# 20210416-JGaylord-FuzzCracklePlus.net
KiCad netlist of a schematic drawn in EAGLE
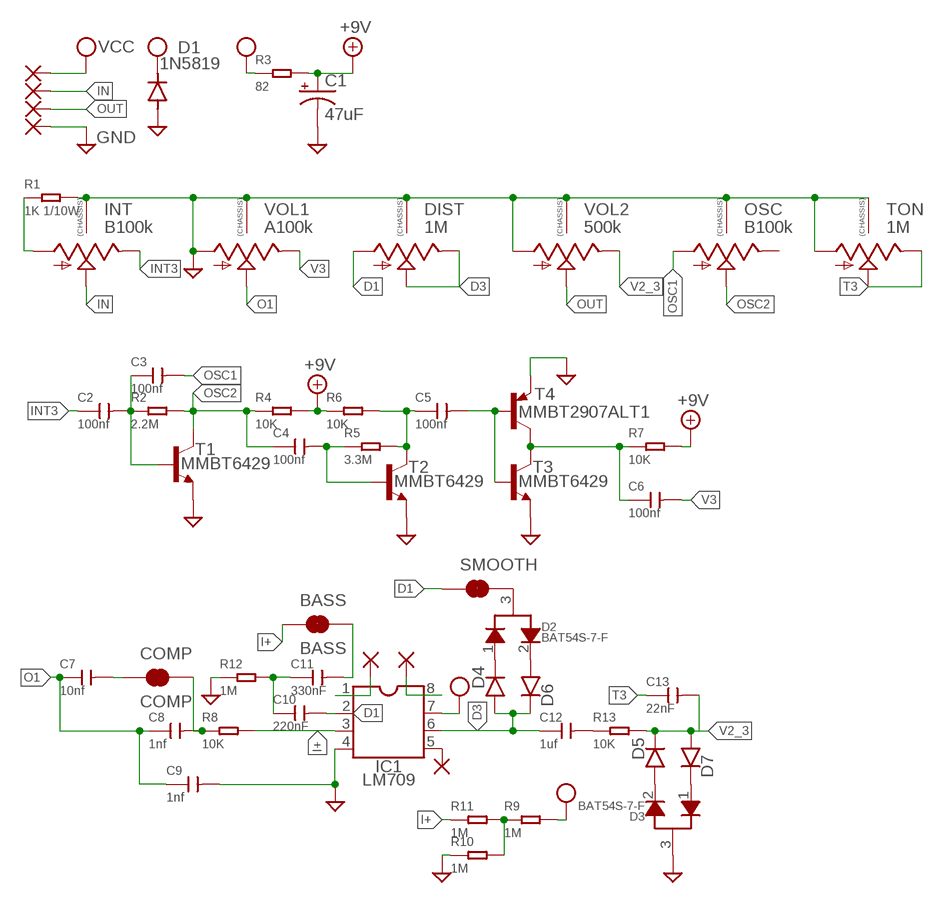
[diagram p0: schematic, sheet 1]

(export (version "E")
  (design (tool "Eeschema 10.0.6"))
  (components
    (comp (ref "BASS")
      (value "BASS")
      (footprint "eagle-import:SMT-JUMPER_2_NC_TRACE_SILK")
      (libsource (lib "eagle-import") (part "JUMPER-SMT_2_NC_TRACE_SILK"))
    )
    (comp (ref "C1")
      (value "47uF")
      (footprint "eagle-import:CPOL-RADIAL-2.5MM-6.5MM")
      (libsource (lib "eagle-import") (part "100UF-POLAR-RADIAL-2.5MM-25V-20%"))
    )
    (comp (ref "C2")
      (value "100nf")
      (footprint "eagle-import:C0603")
      (fields (field (name "MPN") "CC0603KRX7R9BB104"))
      (libsource (lib "eagle-import") (part "CERAMIC-100NF-50V-10%-X7R(0603)"))
    )
    (comp (ref "C3")
      (value "100nf")
      (footprint "eagle-import:C0603")
      (fields (field (name "MPN") "CC0603KRX7R9BB104"))
      (libsource (lib "eagle-import") (part "CERAMIC-100NF-50V-10%-X7R(0603)"))
    )
    (comp (ref "C4")
      (value "100nf")
      (footprint "eagle-import:C0603")
      (fields (field (name "MPN") "CC0603KRX7R9BB104"))
      (libsource (lib "eagle-import") (part "CERAMIC-100NF-50V-10%-X7R(0603)"))
    )
    (comp (ref "C5")
      (value "100nf")
      (footprint "eagle-import:C0603")
      (fields (field (name "MPN") "CC0603KRX7R9BB104"))
      (libsource (lib "eagle-import") (part "CERAMIC-100NF-50V-10%-X7R(0603)"))
    )
    (comp (ref "C6")
      (value "100nf")
      (footprint "eagle-import:C0603")
      (fields (field (name "MPN") "CC0603KRX7R9BB104"))
      (libsource (lib "eagle-import") (part "CERAMIC-100NF-50V-10%-X7R(0603)"))
    )
    (comp (ref "C7")
      (value "10nf")
      (footprint "eagle-import:C0603")
      (fields (field (name "MPN") "CC0603KRX7R9BB104"))
      (libsource (lib "eagle-import") (part "CERAMIC-100NF-50V-10%-X7R(0603)"))
    )
    (comp (ref "C8")
      (value "1nf")
      (footprint "eagle-import:C0603")
      (fields (field (name "MPN") "CC0603KRX7R9BB104"))
      (libsource (lib "eagle-import") (part "CERAMIC-100NF-50V-10%-X7R(0603)"))
    )
    (comp (ref "C9")
      (value "1nf")
      (footprint "eagle-import:C0603")
      (fields (field (name "MPN") "CC0603KRX7R9BB104"))
      (libsource (lib "eagle-import") (part "CERAMIC-100NF-50V-10%-X7R(0603)"))
    )
    (comp (ref "C10")
      (value "220nF")
      (footprint "eagle-import:C0603")
      (fields (field (name "MPN") "CC0603KRX7R9BB104"))
      (libsource (lib "eagle-import") (part "CERAMIC-100NF-50V-10%-X7R(0603)"))
    )
    (comp (ref "C11")
      (value "330nF")
      (footprint "eagle-import:C0603")
      (fields (field (name "MPN") "CC0603KRX7R9BB104"))
      (libsource (lib "eagle-import") (part "CERAMIC-100NF-50V-10%-X7R(0603)"))
    )
    (comp (ref "C12")
      (value "1uf")
      (footprint "eagle-import:C0805")
      (fields (field (name "MPN") "CC0805KKX7R8BB105"))
      (libsource (lib "eagle-import") (part "CERAMIC-1UF-25V-10%-X7R(0805)"))
    )
    (comp (ref "C13")
      (value "22nF")
      (footprint "eagle-import:C0603")
      (fields (field (name "MPN") "CC0603KRX7R9BB104"))
      (libsource (lib "eagle-import") (part "CERAMIC-100NF-50V-10%-X7R(0603)"))
    )
    (comp (ref "COMP")
      (value "COMP")
      (footprint "eagle-import:SMT-JUMPER_2_NC_TRACE_SILK")
      (libsource (lib "eagle-import") (part "JUMPER-SMT_2_NC_TRACE_SILK"))
    )
    (comp (ref "D1")
      (value "1N5819")
      (footprint "eagle-import:SOD123")
      (libsource (lib "eagle-import") (part "DIODE-SOD123"))
    )
    (comp (ref "D2")
      (value "BAT54S-7-F")
      (footprint "eagle-import:SOT23-3")
      (fields
        (field (name "DIGIKEY_PART_NUMBER") "BAT54S-FDITR-ND")
        (field (name "MANUFACTURER") "Diodes Incorporated")
        (field (name "CREATED_BY") "PCBLayout.com")
      )
      (libsource (lib "eagle-import") (part "BAT54S-7-F"))
    )
    (comp (ref "D3")
      (value "BAT54S-7-F")
      (footprint "eagle-import:SOT23-3")
      (fields
        (field (name "DIGIKEY_PART_NUMBER") "BAT54S-FDITR-ND")
        (field (name "MANUFACTURER") "Diodes Incorporated")
        (field (name "CREATED_BY") "PCBLayout.com")
      )
      (libsource (lib "eagle-import") (part "BAT54S-7-F"))
    )
    (comp (ref "D4")
      (value "DO35.1")
      (footprint "eagle-import:DO41-1")
      (libsource (lib "eagle-import") (part "DO35.1"))
    )
    (comp (ref "D5")
      (value "DO35.1")
      (footprint "eagle-import:DO41-1")
      (libsource (lib "eagle-import") (part "DO35.1"))
    )
    (comp (ref "D6")
      (value "DO35.1")
      (footprint "eagle-import:DO41-1")
      (libsource (lib "eagle-import") (part "DO35.1"))
    )
    (comp (ref "D7")
      (value "DO35.1")
      (footprint "eagle-import:DO41-1")
      (libsource (lib "eagle-import") (part "DO35.1"))
    )
    (comp (ref "DIST")
      (value "1M")
      (footprint "eagle-import:9MM_SNAP-IN_POT")
      (libsource (lib "eagle-import") (part "9MM_SNAP-IN_POT_CHASSIS"))
    )
    (comp (ref "IC1")
      (value "LM709")
      (footprint "eagle-import:DIP08")
      (libsource (lib "eagle-import") (part "DIP8_TH"))
    )
    (comp (ref "INT")
      (value "B100k")
      (footprint "eagle-import:9MM_SNAP-IN_POT")
      (libsource (lib "eagle-import") (part "9MM_SNAP-IN_POT_CHASSIS"))
    )
    (comp (ref "NC")
      (value "1,6/0,8")
      (footprint "eagle-import:1,6_0,8")
      (libsource (lib "eagle-import") (part "1,6/0,8"))
    )
    (comp (ref "NC1")
      (value "1,6/0,8")
      (footprint "eagle-import:1,6_0,8")
      (libsource (lib "eagle-import") (part "1,6/0,8"))
    )
    (comp (ref "NC2")
      (value "1,6/0,8")
      (footprint "eagle-import:1,6_0,8")
      (libsource (lib "eagle-import") (part "1,6/0,8"))
    )
    (comp (ref "OSC")
      (value "B100k")
      (footprint "eagle-import:9MM_SNAP-IN_POT")
      (libsource (lib "eagle-import") (part "9MM_SNAP-IN_POT_CHASSIS"))
    )
    (comp (ref "PAD1")
      (value "1,6/0,8")
      (footprint "eagle-import:1,6_0,8")
      (libsource (lib "eagle-import") (part "1,6/0,8"))
    )
    (comp (ref "PAD2")
      (value "1,6/0,8")
      (footprint "eagle-import:1,6_0,8")
      (libsource (lib "eagle-import") (part "1,6/0,8"))
    )
    (comp (ref "PAD3")
      (value "1,6/0,8")
      (footprint "eagle-import:1,6_0,8")
      (libsource (lib "eagle-import") (part "1,6/0,8"))
    )
    (comp (ref "PAD4")
      (value "1,6/0,8")
      (footprint "eagle-import:1,6_0,8")
      (libsource (lib "eagle-import") (part "1,6/0,8"))
    )
    (comp (ref "R1")
      (value "1K 1/10W")
      (footprint "eagle-import:R0603")
      (fields (field (name "MPN") "RC0603JR-071KL"))
      (libsource (lib "eagle-import") (part "SMD-RES-1K-5%-1/10W(0603)"))
    )
    (comp (ref "R2")
      (value "2.2M")
      (footprint "eagle-import:R0603")
      (fields (field (name "MPN") "RC0603FR-072ML"))
      (libsource (lib "eagle-import") (part "SMD-RES-2M-1%-1/10W(0603)"))
    )
    (comp (ref "R3")
      (value "82")
      (footprint "eagle-import:R0603")
      (fields (field (name "MPN") "RC0603FR-071K5L"))
      (libsource (lib "eagle-import") (part "SMD-RES-68R-5%-1/10W(0603)"))
    )
    (comp (ref "R4")
      (value "10K")
      (footprint "eagle-import:R0603")
      (fields (field (name "MPN") "RC0603FR-0710KL"))
      (libsource (lib "eagle-import") (part "SMD-RES-10K-1%-1/10W(0603)"))
    )
    (comp (ref "R5")
      (value "3.3M")
      (footprint "eagle-import:R0603")
      (fields (field (name "MPN") "RC0603FR-072ML"))
      (libsource (lib "eagle-import") (part "SMD-RES-2M-1%-1/10W(0603)"))
    )
    (comp (ref "R6")
      (value "10K")
      (footprint "eagle-import:R0603")
      (fields (field (name "MPN") "RC0603FR-0710KL"))
      (libsource (lib "eagle-import") (part "SMD-RES-10K-1%-1/10W(0603)"))
    )
    (comp (ref "R7")
      (value "10K")
      (footprint "eagle-import:R0603")
      (fields (field (name "MPN") "RC0603FR-0710KL"))
      (libsource (lib "eagle-import") (part "SMD-RES-10K-1%-1/10W(0603)"))
    )
    (comp (ref "R8")
      (value "10K")
      (footprint "eagle-import:R0603")
      (fields (field (name "MPN") "RC0603FR-0710KL"))
      (libsource (lib "eagle-import") (part "SMD-RES-10K-1%-1/10W(0603)"))
    )
    (comp (ref "R9")
      (value "1M")
      (footprint "eagle-import:R0603")
      (fields (field (name "MPN") "RC0603FR-0710KL"))
      (libsource (lib "eagle-import") (part "SMD-RES-10K-1%-1/10W(0603)"))
    )
    (comp (ref "R10")
      (value "1M")
      (footprint "eagle-import:R0603")
      (fields (field (name "MPN") "RC0603FR-0710KL"))
      (libsource (lib "eagle-import") (part "SMD-RES-10K-1%-1/10W(0603)"))
    )
    (comp (ref "R11")
      (value "1M")
      (footprint "eagle-import:R0603")
      (fields (field (name "MPN") "RC0603FR-0710KL"))
      (libsource (lib "eagle-import") (part "SMD-RES-10K-1%-1/10W(0603)"))
    )
    (comp (ref "R12")
      (value "1M")
      (footprint "eagle-import:R0603")
      (fields (field (name "MPN") "RC0603FR-0710KL"))
      (libsource (lib "eagle-import") (part "SMD-RES-10K-1%-1/10W(0603)"))
    )
    (comp (ref "R13")
      (value "10K")
      (footprint "eagle-import:R0603")
      (fields (field (name "MPN") "RC0603FR-0710KL"))
      (libsource (lib "eagle-import") (part "SMD-RES-10K-1%-1/10W(0603)"))
    )
    (comp (ref "SMOOTH")
      (value "JUMPER-SMT_2_NC_TRACE_SILK")
      (footprint "eagle-import:SMT-JUMPER_2_NC_TRACE_SILK")
      (libsource (lib "eagle-import") (part "JUMPER-SMT_2_NC_TRACE_SILK"))
    )
    (comp (ref "T1")
      (value "MMBT6429")
      (footprint "eagle-import:SOT23-BEC")
      (libsource (lib "eagle-import") (part "-NPN-SOT23-BECMMBT6429LT1"))
    )
    (comp (ref "T2")
      (value "MMBT6429")
      (footprint "eagle-import:SOT23-BEC")
      (libsource (lib "eagle-import") (part "-NPN-SOT23-BECMMBT6429LT1"))
    )
    (comp (ref "T3")
      (value "MMBT6429")
      (footprint "eagle-import:SOT23-BEC")
      (libsource (lib "eagle-import") (part "-NPN-SOT23-BECMMBT6429LT1"))
    )
    (comp (ref "T4")
      (value "MMBT2907ALT1")
      (footprint "eagle-import:SOT23-BEC")
      (libsource (lib "eagle-import") (part "-PNP-SOT23-BECMMBT2907ALT1"))
    )
    (comp (ref "TON")
      (value "1M")
      (footprint "eagle-import:9MM_SNAP-IN_POT")
      (libsource (lib "eagle-import") (part "9MM_SNAP-IN_POT_CHASSIS"))
    )
    (comp (ref "VOL1")
      (value "A100k")
      (footprint "eagle-import:9MM_SNAP-IN_POT")
      (libsource (lib "eagle-import") (part "9MM_SNAP-IN_POT_CHASSIS"))
    )
    (comp (ref "VOL2")
      (value "500k")
      (footprint "eagle-import:9MM_SNAP-IN_POT")
      (libsource (lib "eagle-import") (part "9MM_SNAP-IN_POT_CHASSIS"))
    )
  )
  (nets
    (net (code "1") (name "+9V") (class "Default")
      (node (ref "C1") (pin "1") (pinfunction "+_1") (pintype "passive"))
      (node (ref "R3") (pin "2") (pinfunction "2_2") (pintype "passive"))
      (node (ref "R4") (pin "2") (pinfunction "2_2") (pintype "passive"))
      (node (ref "R6") (pin "1") (pinfunction "1_1") (pintype "passive"))
      (node (ref "R7") (pin "2") (pinfunction "2_2") (pintype "passive"))
    )
    (net (code "2") (name "D1") (class "Default")
      (node (ref "C10") (pin "2") (pinfunction "2_2") (pintype "passive"))
      (node (ref "DIST") (pin "1") (pinfunction "A_1") (pintype "passive"))
      (node (ref "IC1") (pin "2") (pinfunction "2_2") (pintype "passive"))
      (node (ref "SMOOTH") (pin "1") (pinfunction "1_1") (pintype "passive"))
    )
    (net (code "3") (name "D3") (class "Default")
      (node (ref "C12") (pin "1") (pinfunction "1_1") (pintype "passive"))
      (node (ref "D4") (pin "A") (pinfunction "A_A") (pintype "passive"))
      (node (ref "D6") (pin "C") (pinfunction "C_C") (pintype "passive"))
      (node (ref "DIST") (pin "2") (pinfunction "S_2") (pintype "passive"))
      (node (ref "DIST") (pin "3") (pinfunction "E_3") (pintype "passive"))
      (node (ref "IC1") (pin "6") (pinfunction "6_6") (pintype "passive"))
    )
    (net (code "4") (name "GND") (class "Default")
      (node (ref "C1") (pin "2") (pinfunction "-_2") (pintype "passive"))
      (node (ref "C9") (pin "2") (pinfunction "2_2") (pintype "passive"))
      (node (ref "D1") (pin "A") (pinfunction "A_A") (pintype "passive"))
      (node (ref "D3") (pin "3") (pinfunction "3_3") (pintype "passive"))
      (node (ref "DIST") (pin "CHASSIS1") (pinfunction "P$1_CHASSIS1") (pintype "passive"))
      (node (ref "DIST") (pin "CHASSIS2") (pinfunction "P$1_CHASSIS2") (pintype "passive"))
      (node (ref "IC1") (pin "4") (pinfunction "4_4") (pintype "passive"))
      (node (ref "INT") (pin "CHASSIS1") (pinfunction "P$1_CHASSIS1") (pintype "passive"))
      (node (ref "INT") (pin "CHASSIS2") (pinfunction "P$1_CHASSIS2") (pintype "passive"))
      (node (ref "OSC") (pin "CHASSIS1") (pinfunction "P$1_CHASSIS1") (pintype "passive"))
      (node (ref "OSC") (pin "CHASSIS2") (pinfunction "P$1_CHASSIS2") (pintype "passive"))
      (node (ref "PAD4") (pin "1") (pinfunction "P_1") (pintype "passive"))
      (node (ref "R1") (pin "2") (pinfunction "2_2") (pintype "passive"))
      (node (ref "R10") (pin "1") (pinfunction "1_1") (pintype "passive"))
      (node (ref "R12") (pin "1") (pinfunction "1_1") (pintype "passive"))
      (node (ref "T1") (pin "E") (pinfunction "E_E") (pintype "passive"))
      (node (ref "T2") (pin "E") (pinfunction "E_E") (pintype "passive"))
      (node (ref "T3") (pin "E") (pinfunction "E_E") (pintype "passive"))
      (node (ref "T4") (pin "E") (pinfunction "E_E") (pintype "passive"))
      (node (ref "TON") (pin "1") (pinfunction "A_1") (pintype "passive"))
      (node (ref "TON") (pin "CHASSIS1") (pinfunction "P$1_CHASSIS1") (pintype "passive"))
      (node (ref "TON") (pin "CHASSIS2") (pinfunction "P$1_CHASSIS2") (pintype "passive"))
      (node (ref "VOL1") (pin "1") (pinfunction "A_1") (pintype "passive"))
      (node (ref "VOL1") (pin "CHASSIS1") (pinfunction "P$1_CHASSIS1") (pintype "passive"))
      (node (ref "VOL1") (pin "CHASSIS2") (pinfunction "P$1_CHASSIS2") (pintype "passive"))
      (node (ref "VOL2") (pin "1") (pinfunction "A_1") (pintype "passive"))
      (node (ref "VOL2") (pin "CHASSIS1") (pinfunction "P$1_CHASSIS1") (pintype "passive"))
      (node (ref "VOL2") (pin "CHASSIS2") (pinfunction "P$1_CHASSIS2") (pintype "passive"))
    )
    (net (code "5") (name "I+") (class "Default")
      (node (ref "BASS") (pin "1") (pinfunction "1_1") (pintype "passive"))
      (node (ref "IC1") (pin "3") (pinfunction "3_3") (pintype "passive"))
      (node (ref "R11") (pin "1") (pinfunction "1_1") (pintype "passive"))
      (node (ref "R8") (pin "2") (pinfunction "2_2") (pintype "passive"))
    )
    (net (code "6") (name "IN") (class "Default")
      (node (ref "INT") (pin "2") (pinfunction "S_2") (pintype "passive"))
      (node (ref "PAD2") (pin "1") (pinfunction "P_1") (pintype "passive"))
    )
    (net (code "7") (name "INT3") (class "Default")
      (node (ref "C2") (pin "1") (pinfunction "1_1") (pintype "passive"))
      (node (ref "INT") (pin "3") (pinfunction "E_3") (pintype "passive"))
    )
    (net (code "8") (name "Net-(BASS-Pad2)") (class "Default")
      (node (ref "BASS") (pin "2") (pinfunction "2_2") (pintype "passive"))
      (node (ref "C11") (pin "2") (pinfunction "2_2") (pintype "passive"))
    )
    (net (code "9") (name "Net-(C2-Pad2)") (class "Default")
      (node (ref "C2") (pin "2") (pinfunction "2_2") (pintype "passive"))
      (node (ref "C3") (pin "1") (pinfunction "1_1") (pintype "passive"))
      (node (ref "R2") (pin "1") (pinfunction "1_1") (pintype "passive"))
      (node (ref "T1") (pin "B") (pinfunction "B_B") (pintype "passive"))
    )
    (net (code "10") (name "Net-(C4-Pad2)") (class "Default")
      (node (ref "C4") (pin "2") (pinfunction "2_2") (pintype "passive"))
      (node (ref "R5") (pin "1") (pinfunction "1_1") (pintype "passive"))
      (node (ref "T2") (pin "B") (pinfunction "B_B") (pintype "passive"))
    )
    (net (code "11") (name "Net-(C5-Pad1)") (class "Default")
      (node (ref "C5") (pin "1") (pinfunction "1_1") (pintype "passive"))
      (node (ref "R5") (pin "2") (pinfunction "2_2") (pintype "passive"))
      (node (ref "R6") (pin "2") (pinfunction "2_2") (pintype "passive"))
      (node (ref "T2") (pin "C") (pinfunction "C_C") (pintype "passive"))
    )
    (net (code "12") (name "Net-(C5-Pad2)") (class "Default")
      (node (ref "C5") (pin "2") (pinfunction "2_2") (pintype "passive"))
      (node (ref "T3") (pin "B") (pinfunction "B_B") (pintype "passive"))
      (node (ref "T4") (pin "B") (pinfunction "B_B") (pintype "passive"))
    )
    (net (code "13") (name "Net-(C6-Pad1)") (class "Default")
      (node (ref "C6") (pin "1") (pinfunction "1_1") (pintype "passive"))
      (node (ref "R7") (pin "1") (pinfunction "1_1") (pintype "passive"))
      (node (ref "T3") (pin "C") (pinfunction "C_C") (pintype "passive"))
      (node (ref "T4") (pin "C") (pinfunction "C_C") (pintype "passive"))
    )
    (net (code "14") (name "Net-(C7-Pad2)") (class "Default")
      (node (ref "C7") (pin "2") (pinfunction "2_2") (pintype "passive"))
      (node (ref "COMP") (pin "1") (pinfunction "1_1") (pintype "passive"))
    )
    (net (code "15") (name "Net-(C8-Pad2)") (class "Default")
      (node (ref "C8") (pin "2") (pinfunction "2_2") (pintype "passive"))
      (node (ref "COMP") (pin "2") (pinfunction "2_2") (pintype "passive"))
      (node (ref "R8") (pin "1") (pinfunction "1_1") (pintype "passive"))
    )
    (net (code "16") (name "Net-(C10-Pad1)") (class "Default")
      (node (ref "C10") (pin "1") (pinfunction "1_1") (pintype "passive"))
      (node (ref "C11") (pin "1") (pinfunction "1_1") (pintype "passive"))
      (node (ref "R12") (pin "2") (pinfunction "2_2") (pintype "passive"))
    )
    (net (code "17") (name "Net-(C12-Pad2)") (class "Default")
      (node (ref "C12") (pin "2") (pinfunction "2_2") (pintype "passive"))
      (node (ref "R13") (pin "1") (pinfunction "1_1") (pintype "passive"))
    )
    (net (code "18") (name "Net-(D2-Pad1)") (class "Default")
      (node (ref "D2") (pin "1") (pinfunction "1_1") (pintype "passive"))
      (node (ref "D4") (pin "C") (pinfunction "C_C") (pintype "passive"))
    )
    (net (code "19") (name "Net-(D2-Pad2)") (class "Default")
      (node (ref "D2") (pin "2") (pinfunction "2_2") (pintype "passive"))
      (node (ref "D6") (pin "A") (pinfunction "A_A") (pintype "passive"))
    )
    (net (code "20") (name "Net-(D2-Pad3)") (class "Default")
      (node (ref "D2") (pin "3") (pinfunction "3_3") (pintype "passive"))
      (node (ref "SMOOTH") (pin "2") (pinfunction "2_2") (pintype "passive"))
    )
    (net (code "21") (name "Net-(D3-Pad1)") (class "Default")
      (node (ref "D3") (pin "1") (pinfunction "1_1") (pintype "passive"))
      (node (ref "D7") (pin "C") (pinfunction "C_C") (pintype "passive"))
    )
    (net (code "22") (name "Net-(D3-Pad2)") (class "Default")
      (node (ref "D3") (pin "2") (pinfunction "2_2") (pintype "passive"))
      (node (ref "D5") (pin "A") (pinfunction "A_A") (pintype "passive"))
    )
    (net (code "23") (name "Net-(INT-A)") (class "Default")
      (node (ref "INT") (pin "1") (pinfunction "A_1") (pintype "passive"))
      (node (ref "R1") (pin "1") (pinfunction "1_1") (pintype "passive"))
    )
    (net (code "24") (name "Net-(NC-P)") (class "Default")
      (node (ref "IC1") (pin "1") (pinfunction "1_1") (pintype "passive"))
      (node (ref "NC") (pin "1") (pinfunction "P_1") (pintype "passive"))
    )
    (net (code "25") (name "Net-(NC1-P)") (class "Default")
      (node (ref "IC1") (pin "8") (pinfunction "8_8") (pintype "passive"))
      (node (ref "NC1") (pin "1") (pinfunction "P_1") (pintype "passive"))
    )
    (net (code "26") (name "Net-(NC2-P)") (class "Default")
      (node (ref "IC1") (pin "5") (pinfunction "5_5") (pintype "passive"))
      (node (ref "NC2") (pin "1") (pinfunction "P_1") (pintype "passive"))
    )
    (net (code "27") (name "Net-(R10-Pad2)") (class "Default")
      (node (ref "R10") (pin "2") (pinfunction "2_2") (pintype "passive"))
      (node (ref "R11") (pin "2") (pinfunction "2_2") (pintype "passive"))
      (node (ref "R9") (pin "1") (pinfunction "1_1") (pintype "passive"))
    )
    (net (code "28") (name "O1") (class "Default")
      (node (ref "C7") (pin "1") (pinfunction "1_1") (pintype "passive"))
      (node (ref "C8") (pin "1") (pinfunction "1_1") (pintype "passive"))
      (node (ref "C9") (pin "1") (pinfunction "1_1") (pintype "passive"))
      (node (ref "VOL1") (pin "2") (pinfunction "S_2") (pintype "passive"))
    )
    (net (code "29") (name "OSC1") (class "Default")
      (node (ref "C3") (pin "2") (pinfunction "2_2") (pintype "passive"))
      (node (ref "OSC") (pin "1") (pinfunction "A_1") (pintype "passive"))
    )
    (net (code "30") (name "OSC2") (class "Default")
      (node (ref "C4") (pin "1") (pinfunction "1_1") (pintype "passive"))
      (node (ref "OSC") (pin "2") (pinfunction "S_2") (pintype "passive"))
      (node (ref "R2") (pin "2") (pinfunction "2_2") (pintype "passive"))
      (node (ref "R4") (pin "1") (pinfunction "1_1") (pintype "passive"))
      (node (ref "T1") (pin "C") (pinfunction "C_C") (pintype "passive"))
    )
    (net (code "31") (name "OUT") (class "Default")
      (node (ref "PAD3") (pin "1") (pinfunction "P_1") (pintype "passive"))
      (node (ref "VOL2") (pin "2") (pinfunction "S_2") (pintype "passive"))
    )
    (net (code "32") (name "T3") (class "Default")
      (node (ref "C13") (pin "1") (pinfunction "1_1") (pintype "passive"))
      (node (ref "TON") (pin "2") (pinfunction "S_2") (pintype "passive"))
      (node (ref "TON") (pin "3") (pinfunction "E_3") (pintype "passive"))
    )
    (net (code "33") (name "V2_3") (class "Default")
      (node (ref "C13") (pin "2") (pinfunction "2_2") (pintype "passive"))
      (node (ref "D5") (pin "C") (pinfunction "C_C") (pintype "passive"))
      (node (ref "D7") (pin "A") (pinfunction "A_A") (pintype "passive"))
      (node (ref "R13") (pin "2") (pinfunction "2_2") (pintype "passive"))
      (node (ref "VOL2") (pin "3") (pinfunction "E_3") (pintype "passive"))
    )
    (net (code "34") (name "V3") (class "Default")
      (node (ref "C6") (pin "2") (pinfunction "2_2") (pintype "passive"))
      (node (ref "VOL1") (pin "3") (pinfunction "E_3") (pintype "passive"))
    )
    (net (code "35") (name "VCC") (class "Default")
      (node (ref "D1") (pin "C") (pinfunction "C_C") (pintype "passive"))
      (node (ref "IC1") (pin "7") (pinfunction "7_7") (pintype "passive"))
      (node (ref "PAD1") (pin "1") (pinfunction "P_1") (pintype "passive"))
      (node (ref "R3") (pin "1") (pinfunction "1_1") (pintype "passive"))
      (node (ref "R9") (pin "2") (pinfunction "2_2") (pintype "passive"))
    )
    (net (code "36") (name "unconnected-(OSC-E-Pad3)") (class "Default")
      (node (ref "OSC") (pin "3") (pinfunction "E_3") (pintype "passive"))
    )
  )
)
